# BatterySource_RelaisOut.net
KiCad netlist of a schematic drawn in Altium Designer
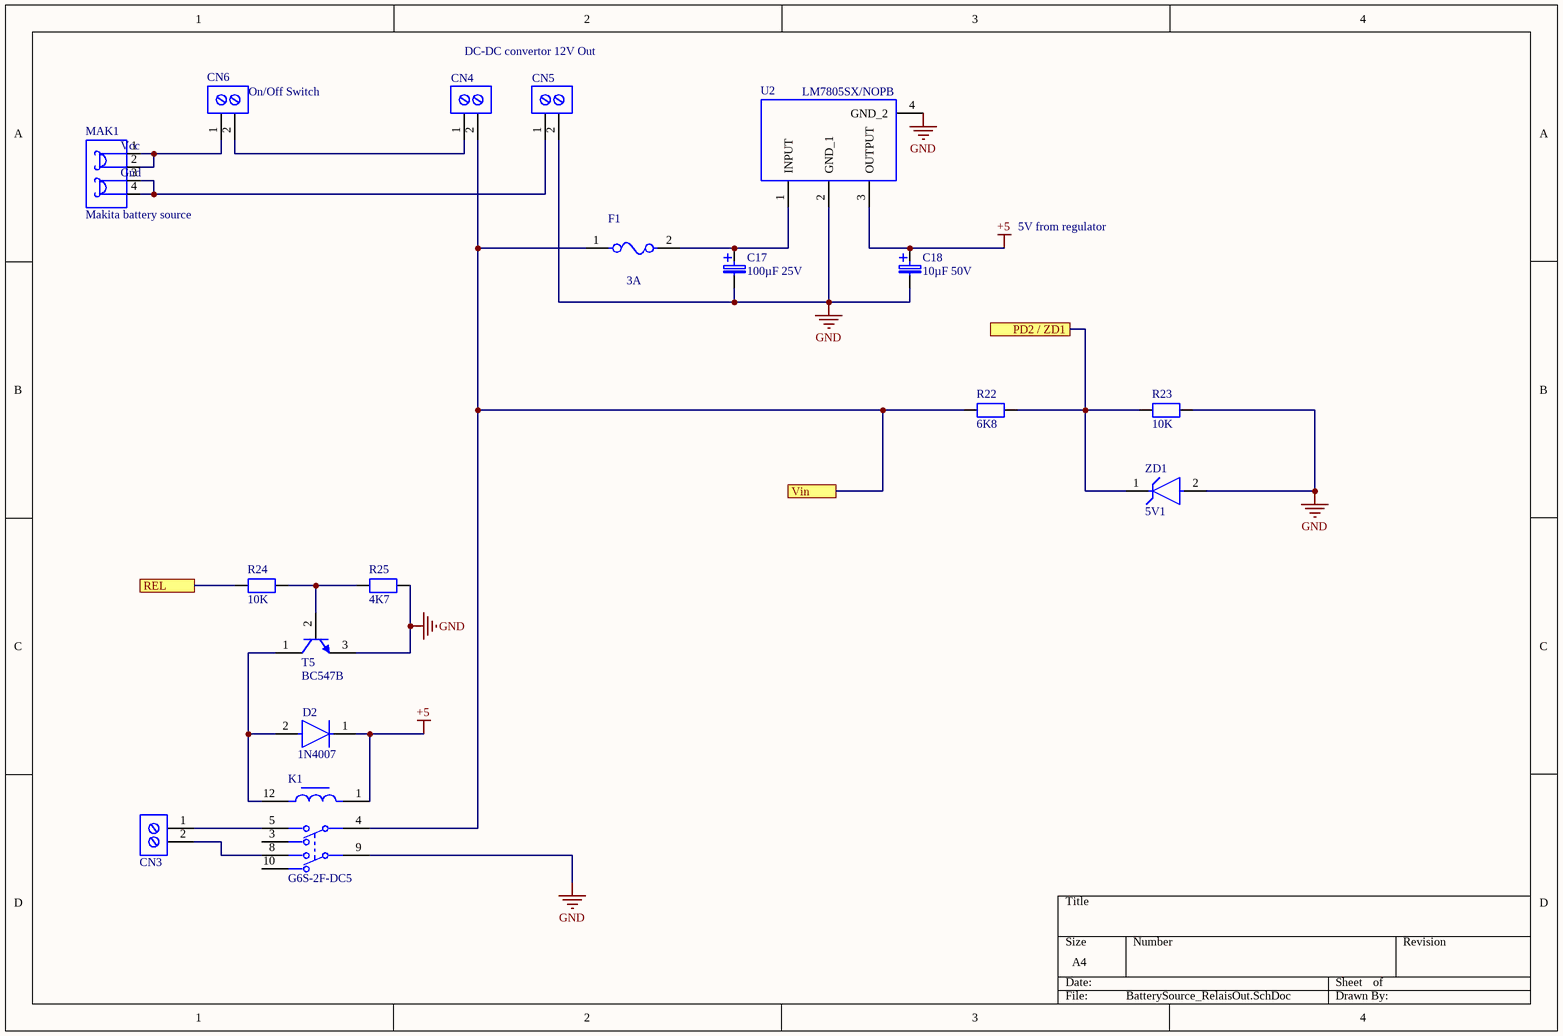
[diagram p0: BatterySource_RelaisOut.SchDoc]

(export (version "E")
  (design (tool "Eeschema 10.0.6"))
  (components
    (comp (ref "C17")
      (value "100µF 25V")
      (footprint "TAP106M050BRW")
      (description "Tantalum Capacitors - Solid Leaded 50V 10uF 20% ESR=1.6 Ohm TAP106M050BRW")
      (fields
        (field (name "MOUSER PART NUMBER") "581-TAP106M050BRW")
        (field (name "MANUFACTURER_PART_NUMBER") "TAP106M050BRW")
      )
      (libsource (lib "SolderStation") (part "capacitor THT radial tantalum"))
    )
    (comp (ref "C18")
      (value "10µF 50V")
      (footprint "TAP106M050BRW")
      (description "Tantalum Capacitors - Solid Leaded 50V 10uF 20% ESR=1.6 Ohm TAP106M050BRW")
      (fields
        (field (name "MOUSER PART NUMBER") "581-TAP106M050BRW")
        (field (name "MANUFACTURER_PART_NUMBER") "TAP106M050BRW")
      )
      (libsource (lib "SolderStation") (part "capacitor THT radial tantalum"))
    )
    (comp (ref "CN3")
      (value "Printkroonsteen 2 POL")
      (footprint "Printkroonsteen 2pin")
      (description "Printkroonsteen 2 PO L1716020000")
      (fields
        (field (name "MANUFACTURER_PART_NUMBER") "1716020000")
        (field (name "MOUSER PART NUMBER") "470-1716020000")
      )
      (libsource (lib "SolderStation") (part "printkroonsteen 1 X 2"))
    )
    (comp (ref "CN4")
      (value "Printkroonsteen 2 POL")
      (footprint "Printkroonsteen 2pin")
      (description "Printkroonsteen 2 PO L1716020000")
      (fields
        (field (name "MANUFACTURER_PART_NUMBER") "1716020000")
        (field (name "MOUSER PART NUMBER") "470-1716020000")
      )
      (libsource (lib "SolderStation") (part "printkroonsteen 1 X 2"))
    )
    (comp (ref "CN5")
      (value "Printkroonsteen 2 POL")
      (footprint "Printkroonsteen 2pin")
      (description "Printkroonsteen 2 PO L1716020000")
      (fields
        (field (name "MANUFACTURER_PART_NUMBER") "1716020000")
        (field (name "MOUSER PART NUMBER") "470-1716020000")
      )
      (libsource (lib "SolderStation") (part "printkroonsteen 1 X 2"))
    )
    (comp (ref "CN6")
      (value "On/Off Switch")
      (footprint "Printkroonsteen 2pin")
      (description "Printkroonsteen 2 PO L1716020000")
      (fields
        (field (name "MANUFACTURER_PART_NUMBER") "1716020000")
        (field (name "MOUSER PART NUMBER") "470-1716020000")
      )
      (libsource (lib "SolderStation") (part "printkroonsteen 1 X 2"))
    )
    (comp (ref "D2")
      (value "1N4007")
      (footprint "DIODE 1N4007 ONSC-AXIAL_LEAD-2-59-10_P")
      (description "DIODE 1N4007 1A 1000V")
      (fields (field (name "MANUFACTURER") "On Semiconductor"))
      (libsource (lib "SolderStation") (part "DIODE 1N4007"))
    )
    (comp (ref "F1")
      (value "3A")
      (footprint "FP-0154-MFG")
      (description "FUSE BRD MNT 4A 125VAC/VDC 2SMDCMP-08605-000003-1")
      (fields
        (field (name "MANUFACTURER PART NUMBER") "0154004.DR")
        (field (name "MANUFACTURER") "Littelfuse")
      )
      (libsource (lib "SolderStation") (part "Fuse"))
    )
    (comp (ref "K1")
      (value "G6S-2F-DC5")
      (footprint "FP-G6S-2F-DC5-MFG")
      (description "RELAY TELECOM DPDT 2A 5V DCCMP-08823-000012-1")
      (fields
        (field (name "MANUFACTURER") "Omron")
        (field (name "OCTOPART") "https://octopart.com/g6s-2f-dc5-omron-85236")
      )
      (libsource (lib "SolderStation") (part "relais 5V 2A"))
    )
    (comp (ref "MAK1")
      (value "Makita battery source")
      (footprint "makita foodprint female spade for PCD")
      (description "complete set-up for bettery makita terminal p/n 644808-8")
      (libsource (lib "SolderStation") (part "Makita battery source"))
    )
    (comp (ref "R22")
      (value "6K8")
      (footprint "RESC2012X50N")
      (fields (field (name "MANUFACTURER") "Vishay Dale") (field (name "PART NUMBER") "CRCW08050000Z0EA"))
      (libsource (lib "SolderStation") (part "resistor 0805"))
    )
    (comp (ref "R23")
      (value "10K")
      (footprint "RESC2012X50N")
      (fields (field (name "MANUFACTURER") "Vishay Dale") (field (name "PART NUMBER") "CRCW08050000Z0EA"))
      (libsource (lib "SolderStation") (part "resistor 0805"))
    )
    (comp (ref "R24")
      (value "10K")
      (footprint "RESC2012X50N")
      (fields (field (name "MANUFACTURER") "Vishay Dale") (field (name "PART NUMBER") "CRCW08050000Z0EA"))
      (libsource (lib "SolderStation") (part "resistor 0805"))
    )
    (comp (ref "R25")
      (value "4K7")
      (footprint "RESC2012X50N")
      (fields (field (name "MANUFACTURER") "Vishay Dale") (field (name "PART NUMBER") "CRCW08050000Z0EA"))
      (libsource (lib "SolderStation") (part "resistor 0805"))
    )
    (comp (ref "T5")
      (value "BC547B")
      (footprint "ONSC-TO-92-3-29-11")
      (description "Amplifier Transistor, NPN Silicon, 3-Pin TO-92, Bulk Box CMP-1048-01467-1")
      (fields (field (name "MANUFACTURER") "On Semiconductor"))
      (libsource (lib "SolderStation") (part "Transistor NPN BC547B THT"))
    )
    (comp (ref "U2")
      (value "LM7805SX/NOPB")
      (footprint "FP-KTT0003B-MFG")
      (description "IC REG LIN 5V 1.5A DDPAK/TO263-3 CMP-2000-07590-2")
      (fields
        (field (name "OCTOPART") "https://octopart.com/lm7805sx%2Fnopb-texas+instruments-74629994")
        (field (name "MANUFACTURER") "Texas Instruments")
      )
      (libsource (lib "SolderStation") (part "VoltageRed LM7805 SMD"))
    )
    (comp (ref "ZD1")
      (value "5V1")
      (footprint "Zenerdiode TH")
      (description "Series 500 mW 5.1 V 200 mA Through Hole Zener Diode - DO-35")
      (fields (field (name "TOLERANCE") "5%"))
      (libsource (lib "SolderStation") (part "ZenerDiode"))
    )
  )
  (nets
    (net (code "1") (name "+5") (class "Default")
      (node (ref "C18") (pin "1") (pinfunction "1_1") (pintype "passive"))
      (node (ref "D2") (pin "1") (pinfunction "C_1") (pintype "passive"))
      (node (ref "K1") (pin "1") (pinfunction "1_1") (pintype "passive"))
      (node (ref "U2") (pin "3") (pinfunction "OUTPUT_3") (pintype "passive"))
    )
    (net (code "2") (name "/PD2 {slash} ZD1") (class "Default")
      (node (ref "R22") (pin "2") (pinfunction "2_2") (pintype "passive"))
      (node (ref "R23") (pin "1") (pinfunction "1_1") (pintype "passive"))
      (node (ref "ZD1") (pin "1") (pinfunction "C_1") (pintype "passive"))
    )
    (net (code "3") (name "/REL") (class "Default")
      (node (ref "R24") (pin "1") (pinfunction "1_1") (pintype "passive"))
    )
    (net (code "4") (name "/Vin") (class "Default")
      (node (ref "CN4") (pin "2") (pinfunction "2_2") (pintype "passive"))
      (node (ref "F1") (pin "1") (pinfunction "1_1") (pintype "passive"))
      (node (ref "K1") (pin "4") (pinfunction "4_4") (pintype "passive"))
      (node (ref "R22") (pin "1") (pinfunction "1_1") (pintype "passive"))
    )
    (net (code "5") (name "GND") (class "Default")
      (node (ref "C17") (pin "2") (pinfunction "2_2") (pintype "passive"))
      (node (ref "C18") (pin "2") (pinfunction "2_2") (pintype "passive"))
      (node (ref "CN5") (pin "2") (pinfunction "2_2") (pintype "passive"))
      (node (ref "K1") (pin "9") (pinfunction "9_9") (pintype "passive"))
      (node (ref "R23") (pin "2") (pinfunction "2_2") (pintype "passive"))
      (node (ref "R25") (pin "2") (pinfunction "2_2") (pintype "passive"))
      (node (ref "T5") (pin "3") (pinfunction "E_3") (pintype "passive"))
      (node (ref "U2") (pin "2") (pinfunction "GND_1_2") (pintype "passive"))
      (node (ref "U2") (pin "4") (pinfunction "GND_2_4") (pintype "power_in"))
      (node (ref "ZD1") (pin "2") (pinfunction "A_2") (pintype "passive"))
    )
    (net (code "6") (name "Net-(CN3-Pad1)") (class "Default")
      (node (ref "CN3") (pin "1") (pinfunction "1_1") (pintype "passive"))
      (node (ref "K1") (pin "5") (pinfunction "5_5") (pintype "passive"))
    )
    (net (code "7") (name "Net-(CN3-Pad2)") (class "Default")
      (node (ref "CN3") (pin "2") (pinfunction "2_2") (pintype "passive"))
      (node (ref "K1") (pin "8") (pinfunction "8_8") (pintype "passive"))
    )
    (net (code "8") (name "Net-(CN4-Pad1)") (class "Default")
      (node (ref "CN4") (pin "1") (pinfunction "1_1") (pintype "passive"))
      (node (ref "CN6") (pin "2") (pinfunction "2_2") (pintype "passive"))
    )
    (net (code "9") (name "Net-(CN5-Pad1)") (class "Default")
      (node (ref "CN5") (pin "1") (pinfunction "1_1") (pintype "passive"))
      (node (ref "MAK1") (pin "3") (pinfunction "3_3") (pintype "passive"))
      (node (ref "MAK1") (pin "4") (pinfunction "4_4") (pintype "passive"))
    )
    (net (code "10") (name "Net-(CN6-Pad1)") (class "Default")
      (node (ref "CN6") (pin "1") (pinfunction "1_1") (pintype "passive"))
      (node (ref "MAK1") (pin "1") (pinfunction "1_1") (pintype "passive"))
      (node (ref "MAK1") (pin "2") (pinfunction "2_2") (pintype "passive"))
    )
    (net (code "11") (name "Net-(D2-A)") (class "Default")
      (node (ref "D2") (pin "2") (pinfunction "A_2") (pintype "passive"))
      (node (ref "K1") (pin "12") (pinfunction "12_12") (pintype "passive"))
      (node (ref "T5") (pin "1") (pinfunction "C_1") (pintype "passive"))
    )
    (net (code "12") (name "Net-(T5-B)") (class "Default")
      (node (ref "R24") (pin "2") (pinfunction "2_2") (pintype "passive"))
      (node (ref "R25") (pin "1") (pinfunction "1_1") (pintype "passive"))
      (node (ref "T5") (pin "2") (pinfunction "B_2") (pintype "passive"))
    )
    (net (code "13") (name "Net-(U2-INPUT)") (class "Default")
      (node (ref "C17") (pin "1") (pinfunction "1_1") (pintype "passive"))
      (node (ref "F1") (pin "2") (pinfunction "2_2") (pintype "passive"))
      (node (ref "U2") (pin "1") (pinfunction "INPUT_1") (pintype "passive"))
    )
    (net (code "14") (name "unconnected-(K1-Pad3)") (class "Default")
      (node (ref "K1") (pin "3") (pinfunction "3_3") (pintype "passive"))
    )
    (net (code "15") (name "unconnected-(K1-Pad10)") (class "Default")
      (node (ref "K1") (pin "10") (pinfunction "10_10") (pintype "passive"))
    )
  )
)
